# USB_OTG_FS.net
KiCad netlist of a schematic drawn in Altium Designer
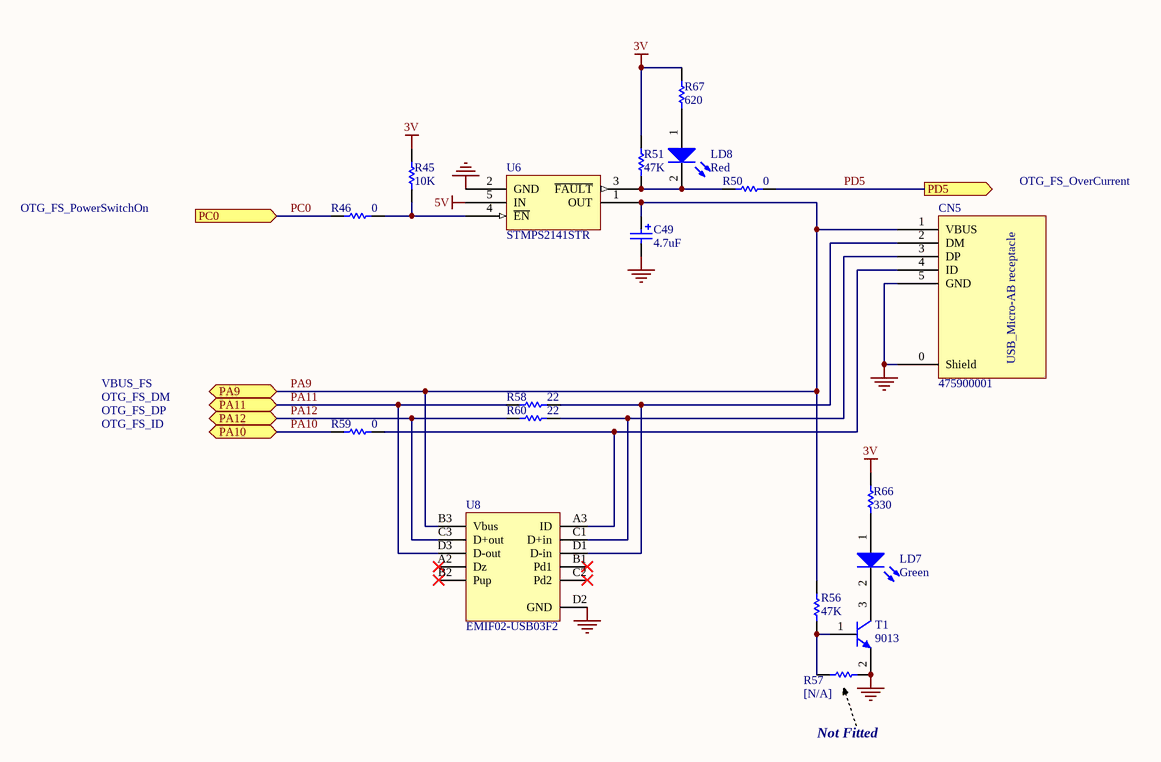
[diagram p0: USB_OTG_FS.SchDoc]

(export (version "E")
  (design (tool "Eeschema 10.0.6"))
  (components
    (comp (ref "C49")
      (value "4.7uF")
      (footprint "CASE-A")
      (description "Polarized Capacitor (Radial)")
      (fields (field (name "PUBLISHER") "Altium Limited"))
      (libsource (lib "Miscellaneous Devices") (part "Cap Pol1"))
    )
    (comp (ref "CN5")
      (value "475900001")
      (footprint "USB-MICRO-AB_new")
      (libsource (lib "MB997") (part "475900001_"))
    )
    (comp (ref "LD7")
      (value "Green")
      (footprint "LED0603")
      (description "Typical RED, GREEN, YELLOW, AMBER GaAs LED")
      (fields (field (name "PUBLISHER") "Altium Limited"))
      (libsource (lib "Miscellaneous Devices") (part "LED2"))
    )
    (comp (ref "LD8")
      (value "Red")
      (footprint "LED0603")
      (description "Typical RED, GREEN, YELLOW, AMBER GaAs LED")
      (fields (field (name "PUBLISHER") "Altium Limited"))
      (libsource (lib "Miscellaneous Devices") (part "LED2"))
    )
    (comp (ref "R45")
      (value "10K")
      (footprint "0402R")
      (description "Resistor")
      (fields (field (name "PUBLISHER") "Altium Limited"))
      (libsource (lib "Miscellaneous Devices") (part "res1"))
    )
    (comp (ref "R46")
      (value "0")
      (footprint "0603R")
      (description "Resistor")
      (fields (field (name "PUBLISHER") "Altium Limited"))
      (libsource (lib "Miscellaneous Devices") (part "Res1"))
    )
    (comp (ref "R50")
      (value "0")
      (footprint "0603R")
      (description "Resistor")
      (fields (field (name "PUBLISHER") "Altium Limited"))
      (libsource (lib "Miscellaneous Devices") (part "Res1"))
    )
    (comp (ref "R51")
      (value "47K")
      (footprint "0402R")
      (description "Resistor")
      (fields (field (name "PUBLISHER") "Altium Limited"))
      (libsource (lib "Miscellaneous Devices") (part "res1"))
    )
    (comp (ref "R56")
      (value "47K")
      (footprint "0402R")
      (description "Resistor")
      (fields (field (name "PUBLISHER") "Altium Limited"))
      (libsource (lib "Miscellaneous Devices") (part "res1"))
    )
    (comp (ref "R57")
      (value "[N/A]")
      (footprint "0603R")
      (description "Resistor")
      (fields (field (name "PUBLISHER") "Altium Limited"))
      (libsource (lib "Miscellaneous Devices") (part "res1"))
    )
    (comp (ref "R58")
      (value "22")
      (footprint "0402R")
      (description "Resistor")
      (fields (field (name "PUBLISHER") "Altium Limited"))
      (libsource (lib "Miscellaneous Devices") (part "Res1"))
    )
    (comp (ref "R59")
      (value "0")
      (footprint "0603R")
      (description "Resistor")
      (fields (field (name "PUBLISHER") "Altium Limited"))
      (libsource (lib "Miscellaneous Devices") (part "Res1"))
    )
    (comp (ref "R60")
      (value "22")
      (footprint "0402R")
      (description "Resistor")
      (fields (field (name "PUBLISHER") "Altium Limited"))
      (libsource (lib "Miscellaneous Devices") (part "Res1"))
    )
    (comp (ref "R66")
      (value "330")
      (footprint "0603R")
      (description "Resistor")
      (fields (field (name "PUBLISHER") "Altium Limited"))
      (libsource (lib "Miscellaneous Devices") (part "res1"))
    )
    (comp (ref "R67")
      (value "620")
      (footprint "0603R")
      (description "Resistor")
      (fields (field (name "PUBLISHER") "Altium Limited"))
      (libsource (lib "Miscellaneous Devices") (part "Res1"))
    )
    (comp (ref "T1")
      (value "9013")
      (footprint "SOT23")
      (description "NPN Bipolar Transistor")
      (fields (field (name "PUBLISHER") "Altium Limited"))
      (libsource (lib "MB997") (part "NPN_NEW"))
    )
    (comp (ref "U6")
      (value "STMPS2141STR")
      (footprint "SOT-23-5L")
      (description "Enhanced single channel power switches")
      (libsource (lib "MB997") (part "STMPS2141STR"))
    )
    (comp (ref "U8")
      (value "EMIF02-USB03F2")
      (footprint "FLIPCHIP(11)")
      (description "2-line IPAD, EMI filter including ESD protection")
      (libsource (lib "MB997") (part "EMIF02-USB03F2"))
    )
  )
  (nets
    (net (code "1") (name "/PA9") (class "Default")
      (node (ref "C49") (pin "1") (pinfunction "1_1") (pintype "passive"))
      (node (ref "CN5") (pin "1") (pinfunction "VBUS_1") (pintype "passive"))
      (node (ref "R56") (pin "2") (pinfunction "2_2") (pintype "passive"))
      (node (ref "U6") (pin "1") (pinfunction "OUT_1") (pintype "passive"))
      (node (ref "U8") (pin "B3") (pinfunction "Vbus_B3") (pintype "passive"))
    )
    (net (code "2") (name "/PA10") (class "Default")
      (node (ref "R59") (pin "2") (pinfunction "2_2") (pintype "passive"))
    )
    (net (code "3") (name "/PA11") (class "Default")
      (node (ref "R58") (pin "2") (pinfunction "2_2") (pintype "passive"))
      (node (ref "U8") (pin "D3") (pinfunction "D-out_D3") (pintype "passive"))
    )
    (net (code "4") (name "/PA12") (class "Default")
      (node (ref "R60") (pin "2") (pinfunction "2_2") (pintype "passive"))
      (node (ref "U8") (pin "C3") (pinfunction "D+out_C3") (pintype "passive"))
    )
    (net (code "5") (name "/PC0") (class "Default")
      (node (ref "R46") (pin "2") (pinfunction "2_2") (pintype "passive"))
    )
    (net (code "6") (name "/PD5") (class "Default")
      (node (ref "R50") (pin "1") (pinfunction "1_1") (pintype "passive"))
    )
    (net (code "7") (name "3V") (class "Default")
      (node (ref "R45") (pin "1") (pinfunction "1_1") (pintype "passive"))
      (node (ref "R51") (pin "1") (pinfunction "1_1") (pintype "passive"))
      (node (ref "R66") (pin "2") (pinfunction "2_2") (pintype "passive"))
      (node (ref "R67") (pin "2") (pinfunction "2_2") (pintype "passive"))
    )
    (net (code "8") (name "5V") (class "Default")
      (node (ref "U6") (pin "5") (pinfunction "IN_5") (pintype "passive"))
    )
    (net (code "9") (name "GND") (class "Default")
      (node (ref "C49") (pin "2") (pinfunction "2_2") (pintype "passive"))
      (node (ref "CN5") (pin "0") (pinfunction "Shield_0") (pintype "passive"))
      (node (ref "CN5") (pin "5") (pinfunction "GND_5") (pintype "passive"))
      (node (ref "R57") (pin "1") (pinfunction "1_1") (pintype "passive"))
      (node (ref "T1") (pin "2") (pinfunction "E_2") (pintype "passive"))
      (node (ref "U6") (pin "2") (pinfunction "GND_2") (pintype "passive"))
      (node (ref "U8") (pin "D2") (pinfunction "GND_D2") (pintype "passive"))
    )
    (net (code "10") (name "Net-(CN5-DM)") (class "Default")
      (node (ref "CN5") (pin "2") (pinfunction "DM_2") (pintype "passive"))
      (node (ref "R58") (pin "1") (pinfunction "1_1") (pintype "passive"))
      (node (ref "U8") (pin "D1") (pinfunction "D-in_D1") (pintype "passive"))
    )
    (net (code "11") (name "Net-(CN5-DP)") (class "Default")
      (node (ref "CN5") (pin "3") (pinfunction "DP_3") (pintype "passive"))
      (node (ref "R60") (pin "1") (pinfunction "1_1") (pintype "passive"))
      (node (ref "U8") (pin "C1") (pinfunction "D+in_C1") (pintype "passive"))
    )
    (net (code "12") (name "Net-(CN5-ID)") (class "Default")
      (node (ref "CN5") (pin "4") (pinfunction "ID_4") (pintype "passive"))
      (node (ref "R59") (pin "1") (pinfunction "1_1") (pintype "passive"))
      (node (ref "U8") (pin "A3") (pinfunction "ID_A3") (pintype "passive"))
    )
    (net (code "13") (name "Net-(LD7-A)") (class "Default")
      (node (ref "LD7") (pin "1") (pinfunction "A_1") (pintype "passive"))
      (node (ref "R66") (pin "1") (pinfunction "1_1") (pintype "passive"))
    )
    (net (code "14") (name "Net-(LD7-K)") (class "Default")
      (node (ref "LD7") (pin "2") (pinfunction "K_2") (pintype "passive"))
      (node (ref "T1") (pin "3") (pinfunction "C_3") (pintype "passive"))
    )
    (net (code "15") (name "Net-(LD8-A)") (class "Default")
      (node (ref "LD8") (pin "1") (pinfunction "A_1") (pintype "passive"))
      (node (ref "R67") (pin "1") (pinfunction "1_1") (pintype "passive"))
    )
    (net (code "16") (name "Net-(LD8-K)") (class "Default")
      (node (ref "LD8") (pin "2") (pinfunction "K_2") (pintype "passive"))
      (node (ref "R50") (pin "2") (pinfunction "2_2") (pintype "passive"))
      (node (ref "R51") (pin "2") (pinfunction "2_2") (pintype "passive"))
      (node (ref "U6") (pin "3") (pinfunction "~{FAULT}_3") (pintype "output"))
    )
    (net (code "17") (name "Net-(T1-B)") (class "Default")
      (node (ref "R56") (pin "1") (pinfunction "1_1") (pintype "passive"))
      (node (ref "R57") (pin "2") (pinfunction "2_2") (pintype "passive"))
      (node (ref "T1") (pin "1") (pinfunction "B_1") (pintype "passive"))
    )
    (net (code "18") (name "Net-(U6-~{EN})") (class "Default")
      (node (ref "R45") (pin "2") (pinfunction "2_2") (pintype "passive"))
      (node (ref "R46") (pin "1") (pinfunction "1_1") (pintype "passive"))
      (node (ref "U6") (pin "4") (pinfunction "~{EN}_4") (pintype "input"))
    )
    (net (code "19") (name "unconnected-(U8-Dz-PadA2)") (class "Default")
      (node (ref "U8") (pin "A2") (pinfunction "Dz_A2") (pintype "passive+no_connect"))
    )
    (net (code "20") (name "unconnected-(U8-Pd1-PadB1)") (class "Default")
      (node (ref "U8") (pin "B1") (pinfunction "Pd1_B1") (pintype "passive+no_connect"))
    )
    (net (code "21") (name "unconnected-(U8-Pd2-PadC2)") (class "Default")
      (node (ref "U8") (pin "C2") (pinfunction "Pd2_C2") (pintype "passive+no_connect"))
    )
    (net (code "22") (name "unconnected-(U8-Pup-PadB2)") (class "Default")
      (node (ref "U8") (pin "B2") (pinfunction "Pup_B2") (pintype "passive+no_connect"))
    )
  )
)
